# PATHOS_SOM_Power.net
KiCad netlist of a schematic drawn in Altium Designer
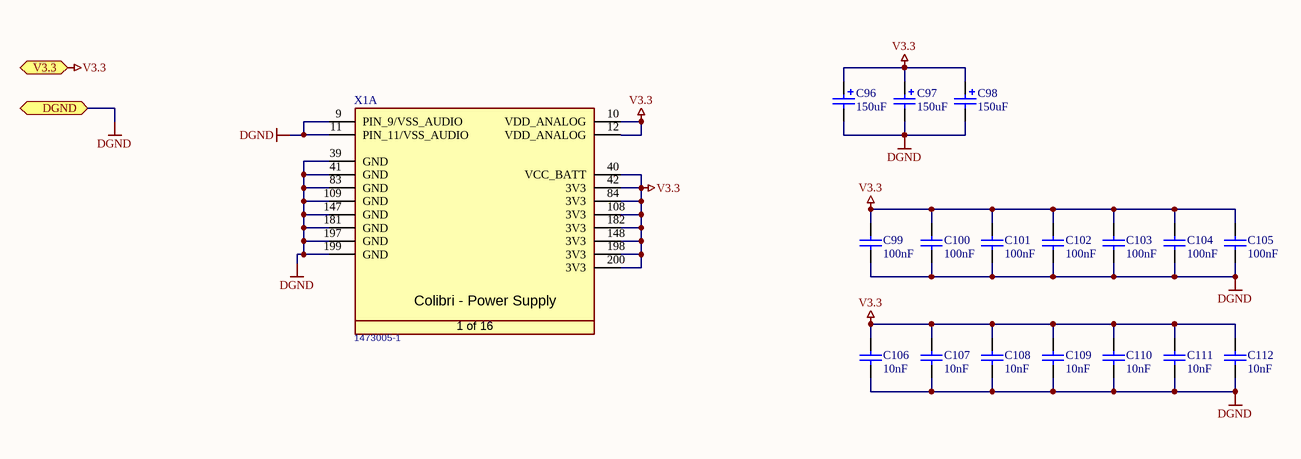
[diagram p0: PATHOS_SOM_Power.SchDoc]

(export (version "E")
  (design (tool "Eeschema 10.0.6"))
  (components
    (comp (ref "C96")
      (value "150uF")
      (footprint "ChipC_7343-40")
      (description "Polarized Capacitor Positive Mark Bar")
      (fields (field (name "#PUBLISHER") "Dr. A. Heinzelmann"))
      (libsource (lib "ELE-LIB") (part "C_POL"))
    )
    (comp (ref "C97")
      (value "150uF")
      (footprint "ChipC_7343-40")
      (description "Polarized Capacitor Positive Mark Bar")
      (fields (field (name "#PUBLISHER") "Dr. A. Heinzelmann"))
      (libsource (lib "ELE-LIB") (part "C_POL"))
    )
    (comp (ref "C98")
      (value "150uF")
      (footprint "ChipC_7343-40")
      (description "Polarized Capacitor Positive Mark Bar")
      (fields (field (name "#PUBLISHER") "Dr. A. Heinzelmann"))
      (libsource (lib "ELE-LIB") (part "C_POL"))
    )
    (comp (ref "C99")
      (value "100nF")
      (footprint "0603_3D")
      (description "Capacitor")
      (fields (field (name "#PUBLISHER") "Dr. A. Heinzelmann"))
      (libsource (lib "EFS_Sensorboard") (part "C"))
    )
    (comp (ref "C100")
      (value "100nF")
      (footprint "0603_3D")
      (description "Capacitor")
      (fields (field (name "#PUBLISHER") "Dr. A. Heinzelmann"))
      (libsource (lib "EFS_Sensorboard") (part "C"))
    )
    (comp (ref "C101")
      (value "100nF")
      (footprint "0603_3D")
      (description "Capacitor")
      (fields (field (name "#PUBLISHER") "Dr. A. Heinzelmann"))
      (libsource (lib "EFS_Sensorboard") (part "C"))
    )
    (comp (ref "C102")
      (value "100nF")
      (footprint "0603_3D")
      (description "Capacitor")
      (fields (field (name "#PUBLISHER") "Dr. A. Heinzelmann"))
      (libsource (lib "EFS_Sensorboard") (part "C"))
    )
    (comp (ref "C103")
      (value "100nF")
      (footprint "0603_3D")
      (description "Capacitor")
      (fields (field (name "#PUBLISHER") "Dr. A. Heinzelmann"))
      (libsource (lib "EFS_Sensorboard") (part "C"))
    )
    (comp (ref "C104")
      (value "100nF")
      (footprint "0603_3D")
      (description "Capacitor")
      (fields (field (name "#PUBLISHER") "Dr. A. Heinzelmann"))
      (libsource (lib "EFS_Sensorboard") (part "C"))
    )
    (comp (ref "C105")
      (value "100nF")
      (footprint "0603_3D")
      (description "Capacitor")
      (fields (field (name "#PUBLISHER") "Dr. A. Heinzelmann"))
      (libsource (lib "EFS_Sensorboard") (part "C"))
    )
    (comp (ref "C106")
      (value "10nF")
      (footprint "0603_3D")
      (description "Capacitor")
      (fields (field (name "#PUBLISHER") "Dr. A. Heinzelmann"))
      (libsource (lib "EFS_Sensorboard") (part "C"))
    )
    (comp (ref "C107")
      (value "10nF")
      (footprint "0603_3D")
      (description "Capacitor")
      (fields (field (name "#PUBLISHER") "Dr. A. Heinzelmann"))
      (libsource (lib "EFS_Sensorboard") (part "C"))
    )
    (comp (ref "C108")
      (value "10nF")
      (footprint "0603_3D")
      (description "Capacitor")
      (fields (field (name "#PUBLISHER") "Dr. A. Heinzelmann"))
      (libsource (lib "EFS_Sensorboard") (part "C"))
    )
    (comp (ref "C109")
      (value "10nF")
      (footprint "0603_3D")
      (description "Capacitor")
      (fields (field (name "#PUBLISHER") "Dr. A. Heinzelmann"))
      (libsource (lib "EFS_Sensorboard") (part "C"))
    )
    (comp (ref "C110")
      (value "10nF")
      (footprint "0603_3D")
      (description "Capacitor")
      (fields (field (name "#PUBLISHER") "Dr. A. Heinzelmann"))
      (libsource (lib "EFS_Sensorboard") (part "C"))
    )
    (comp (ref "C111")
      (value "10nF")
      (footprint "0603_3D")
      (description "Capacitor")
      (fields (field (name "#PUBLISHER") "Dr. A. Heinzelmann"))
      (libsource (lib "EFS_Sensorboard") (part "C"))
    )
    (comp (ref "C112")
      (value "10nF")
      (footprint "0603_3D")
      (description "Capacitor")
      (fields (field (name "#PUBLISHER") "Dr. A. Heinzelmann"))
      (libsource (lib "EFS_Sensorboard") (part "C"))
    )
    (comp (ref "X1")
      (value "CON-Tyco-1473005-1-200-0.6mm")
      (footprint "T_Tyco_1473005-1")
      (description "SODIMM Connector")
      (fields (field (name "MANUFACTURER PART NO.") "1473005-1"))
      (libsource (lib "EFS_Sensorboard") (part "CON-Tyco-1473005-1-200-0.6mm"))
    )
  )
  (nets
    (net (code "1") (name "DGND") (class "Default")
      (node (ref "C100") (pin "1") (pinfunction "1_1") (pintype "passive"))
      (node (ref "C101") (pin "1") (pinfunction "1_1") (pintype "passive"))
      (node (ref "C102") (pin "1") (pinfunction "1_1") (pintype "passive"))
      (node (ref "C103") (pin "1") (pinfunction "1_1") (pintype "passive"))
      (node (ref "C104") (pin "1") (pinfunction "1_1") (pintype "passive"))
      (node (ref "C105") (pin "1") (pinfunction "1_1") (pintype "passive"))
      (node (ref "C106") (pin "1") (pinfunction "1_1") (pintype "passive"))
      (node (ref "C107") (pin "1") (pinfunction "1_1") (pintype "passive"))
      (node (ref "C108") (pin "1") (pinfunction "1_1") (pintype "passive"))
      (node (ref "C109") (pin "1") (pinfunction "1_1") (pintype "passive"))
      (node (ref "C110") (pin "1") (pinfunction "1_1") (pintype "passive"))
      (node (ref "C111") (pin "1") (pinfunction "1_1") (pintype "passive"))
      (node (ref "C112") (pin "1") (pinfunction "1_1") (pintype "passive"))
      (node (ref "C96") (pin "2") (pinfunction "Neg_2") (pintype "passive"))
      (node (ref "C97") (pin "2") (pinfunction "Neg_2") (pintype "passive"))
      (node (ref "C98") (pin "2") (pinfunction "Neg_2") (pintype "passive"))
      (node (ref "C99") (pin "1") (pinfunction "1_1") (pintype "passive"))
      (node (ref "X1") (pin "109") (pinfunction "GND_109") (pintype "power_in"))
      (node (ref "X1") (pin "11") (pinfunction "PIN_11/VSS_AUDIO_11") (pintype "passive"))
      (node (ref "X1") (pin "147") (pinfunction "GND_147") (pintype "power_in"))
      (node (ref "X1") (pin "181") (pinfunction "GND_181") (pintype "power_in"))
      (node (ref "X1") (pin "197") (pinfunction "GND_197") (pintype "power_in"))
      (node (ref "X1") (pin "199") (pinfunction "GND_199") (pintype "power_in"))
      (node (ref "X1") (pin "39") (pinfunction "GND_39") (pintype "power_in"))
      (node (ref "X1") (pin "41") (pinfunction "GND_41") (pintype "power_in"))
      (node (ref "X1") (pin "83") (pinfunction "GND_83") (pintype "power_in"))
      (node (ref "X1") (pin "9") (pinfunction "PIN_9/VSS_AUDIO_9") (pintype "passive"))
    )
    (net (code "2") (name "V3.3") (class "Default")
      (node (ref "C100") (pin "2") (pinfunction "2_2") (pintype "passive"))
      (node (ref "C101") (pin "2") (pinfunction "2_2") (pintype "passive"))
      (node (ref "C102") (pin "2") (pinfunction "2_2") (pintype "passive"))
      (node (ref "C103") (pin "2") (pinfunction "2_2") (pintype "passive"))
      (node (ref "C104") (pin "2") (pinfunction "2_2") (pintype "passive"))
      (node (ref "C105") (pin "2") (pinfunction "2_2") (pintype "passive"))
      (node (ref "C106") (pin "2") (pinfunction "2_2") (pintype "passive"))
      (node (ref "C107") (pin "2") (pinfunction "2_2") (pintype "passive"))
      (node (ref "C108") (pin "2") (pinfunction "2_2") (pintype "passive"))
      (node (ref "C109") (pin "2") (pinfunction "2_2") (pintype "passive"))
      (node (ref "C110") (pin "2") (pinfunction "2_2") (pintype "passive"))
      (node (ref "C111") (pin "2") (pinfunction "2_2") (pintype "passive"))
      (node (ref "C112") (pin "2") (pinfunction "2_2") (pintype "passive"))
      (node (ref "C96") (pin "1") (pinfunction "Pos_1") (pintype "passive"))
      (node (ref "C97") (pin "1") (pinfunction "Pos_1") (pintype "passive"))
      (node (ref "C98") (pin "1") (pinfunction "Pos_1") (pintype "passive"))
      (node (ref "C99") (pin "2") (pinfunction "2_2") (pintype "passive"))
      (node (ref "X1") (pin "10") (pinfunction "VDD_ANALOG_10") (pintype "passive"))
      (node (ref "X1") (pin "108") (pinfunction "3V3_108") (pintype "passive"))
      (node (ref "X1") (pin "12") (pinfunction "VDD_ANALOG_12") (pintype "passive"))
      (node (ref "X1") (pin "148") (pinfunction "3V3_148") (pintype "passive"))
      (node (ref "X1") (pin "182") (pinfunction "3V3_182") (pintype "power_in"))
      (node (ref "X1") (pin "198") (pinfunction "3V3_198") (pintype "power_in"))
      (node (ref "X1") (pin "200") (pinfunction "3V3_200") (pintype "power_in"))
      (node (ref "X1") (pin "40") (pinfunction "VCC_BATT_40") (pintype "power_in"))
      (node (ref "X1") (pin "42") (pinfunction "3V3_42") (pintype "power_in"))
      (node (ref "X1") (pin "84") (pinfunction "3V3_84") (pintype "power_in"))
    )
  )
)
